# Drury-DABSC.net
KiCad netlist of a schematic drawn in EAGLE
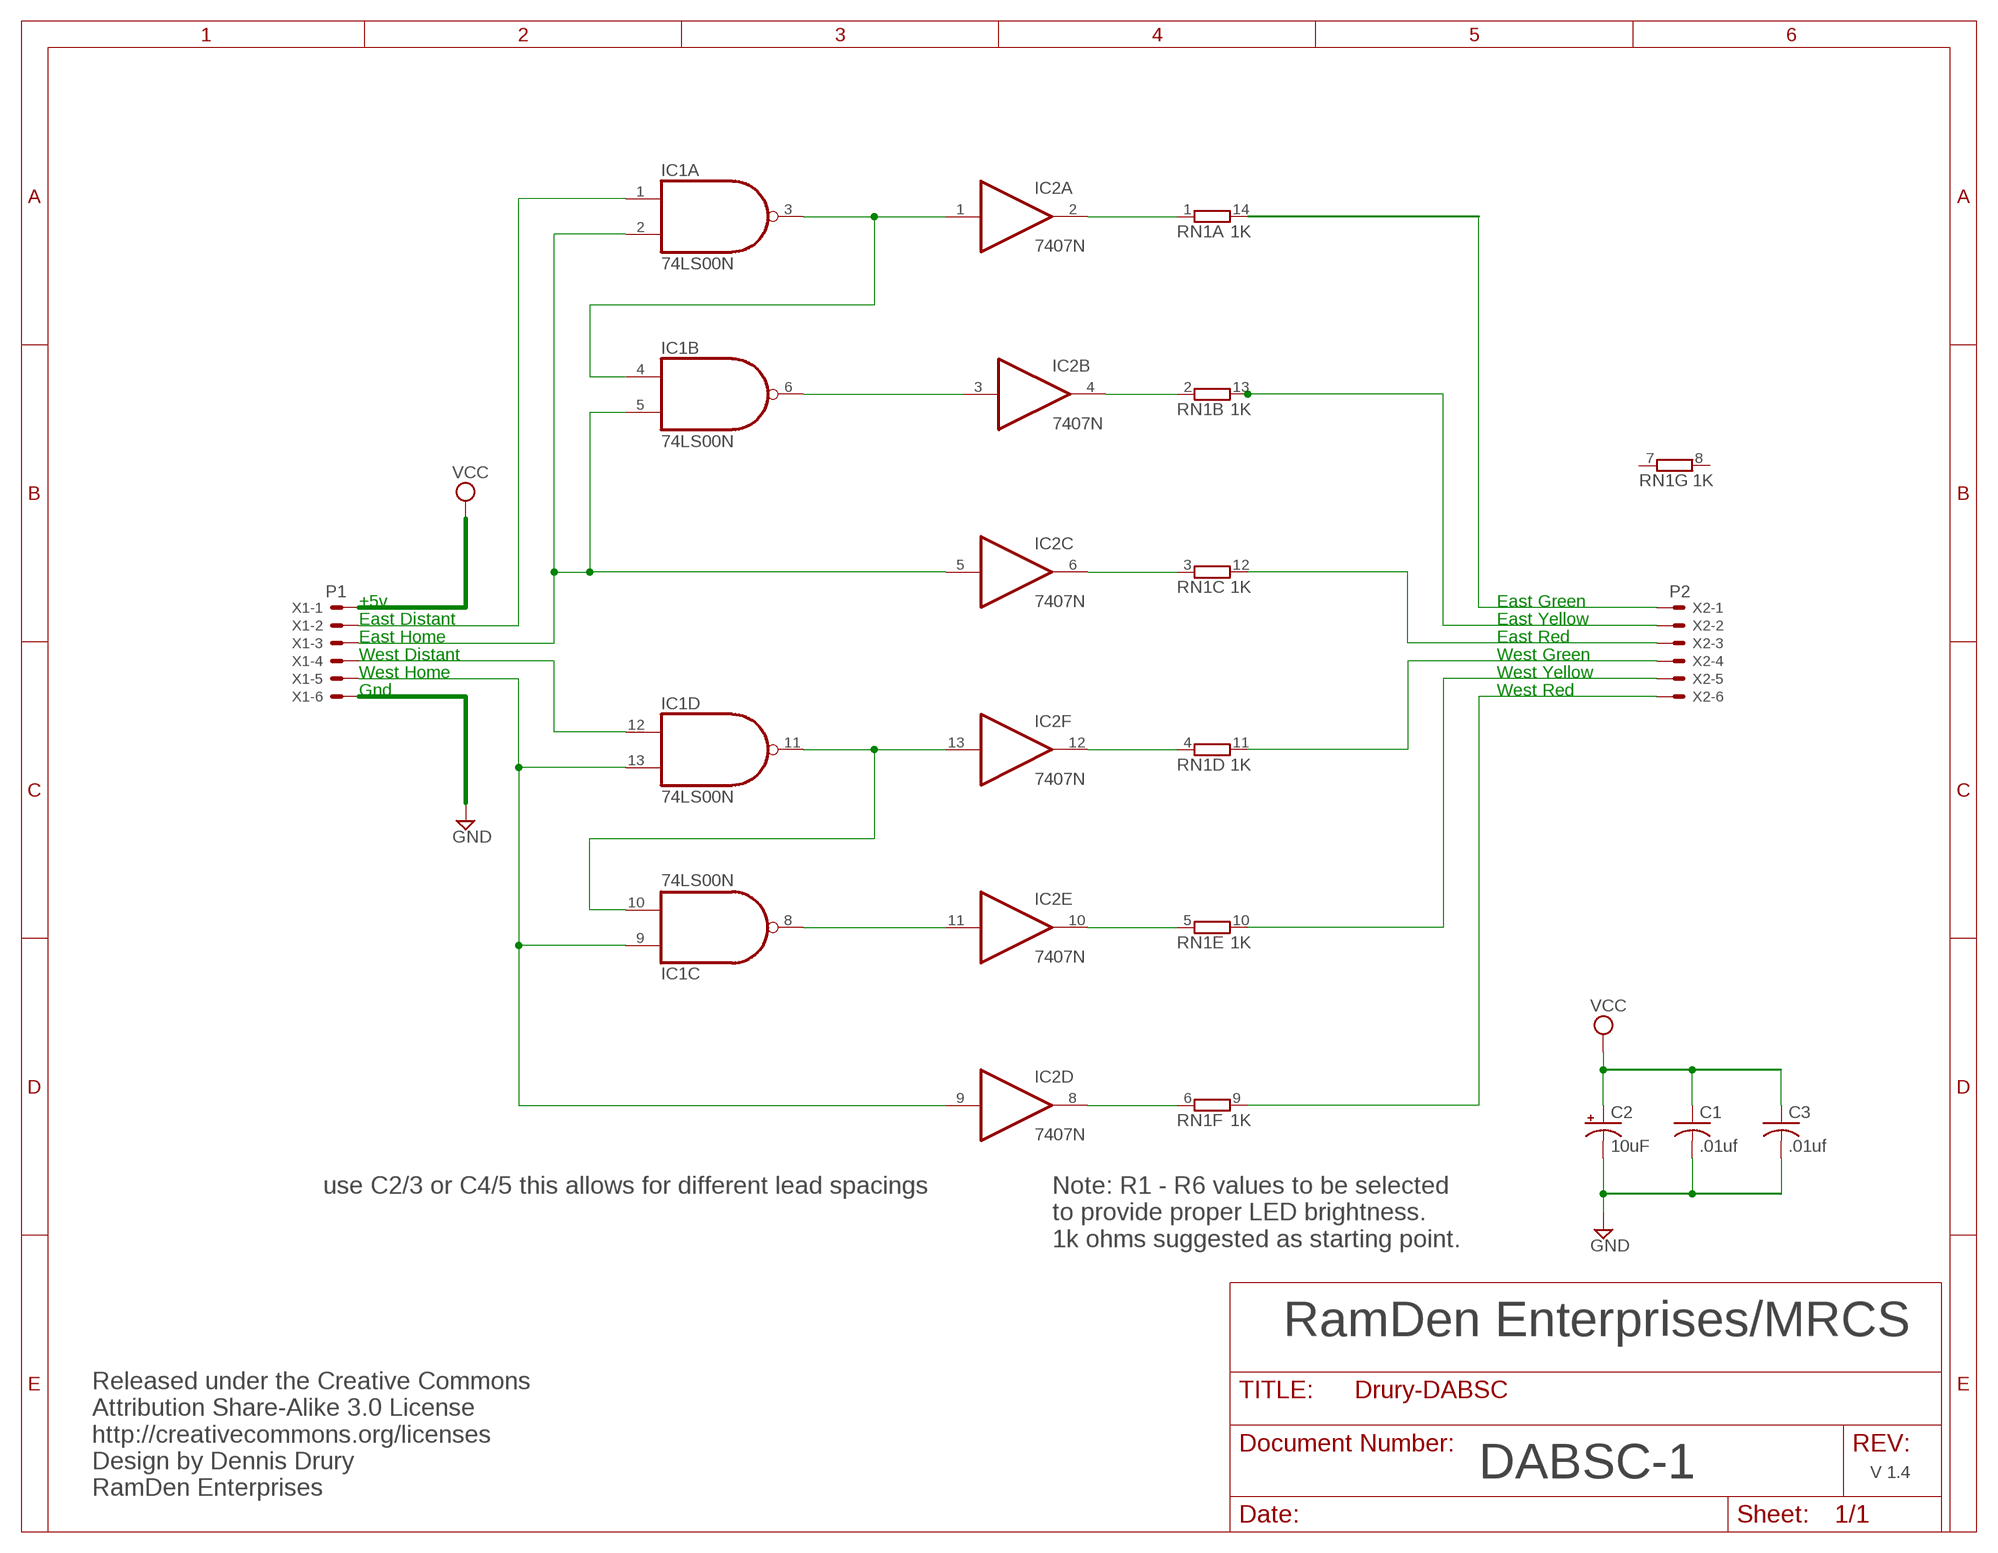
[diagram p0: schematic, sheet 1]

(export (version "E")
  (design (tool "Eeschema 10.0.6"))
  (components
    (comp (ref "C1")
      (value ".01uf")
      (footprint "eagle-import:C050-025X075")
      (libsource (lib "eagle-import") (part "C-US050-025X075"))
    )
    (comp (ref "C2")
      (value "10uF")
      (footprint "eagle-import:E2-5")
      (libsource (lib "eagle-import") (part "CAP-POLPTH-2MM"))
    )
    (comp (ref "C3")
      (value ".01uf")
      (footprint "eagle-import:C050-025X075")
      (libsource (lib "eagle-import") (part "C-US050-025X075"))
    )
    (comp (ref "IC1")
      (value "74LS00N")
      (footprint "eagle-import:DIL14")
      (libsource (lib "eagle-import") (part "7400NLS"))
    )
    (comp (ref "IC2")
      (value "7407N")
      (footprint "eagle-import:DIL14")
      (libsource (lib "eagle-import") (part "7407N"))
    )
    (comp (ref "RN1")
      (value "1K")
      (footprint "eagle-import:DIL14")
      (libsource (lib "eagle-import") (part "7R-N"))
    )
    (comp (ref "X1")
      (value "P1")
      (footprint "eagle-import:22-23-2061")
      (fields (field (name "MF") "MOLEX") (field (name "MPN") "22-23-2061"))
      (libsource (lib "eagle-import") (part "22-23-2061"))
    )
    (comp (ref "X2")
      (value "P2")
      (footprint "eagle-import:22-23-2061")
      (fields (field (name "MF") "MOLEX") (field (name "MPN") "22-23-2061"))
      (libsource (lib "eagle-import") (part "22-23-2061"))
    )
  )
  (nets
    (net (code "1") (name "GND") (class "Default")
      (node (ref "C1") (pin "2") (pinfunction "2_2") (pintype "passive"))
      (node (ref "C2") (pin "-") (pinfunction "-_-") (pintype "passive"))
      (node (ref "C3") (pin "2") (pinfunction "2_2") (pintype "passive"))
      (node (ref "X1") (pin "6") (pinfunction "S_6") (pintype "passive"))
    )
    (net (code "2") (name "Net-(IC1A-I0)") (class "Default")
      (node (ref "IC1") (pin "1") (pinfunction "I0_1") (pintype "input"))
      (node (ref "X1") (pin "2") (pinfunction "S_2") (pintype "passive"))
    )
    (net (code "3") (name "Net-(IC1A-I1)") (class "Default")
      (node (ref "IC1") (pin "2") (pinfunction "I1_2") (pintype "input"))
      (node (ref "IC1") (pin "5") (pinfunction "I1_5") (pintype "input"))
      (node (ref "IC2") (pin "5") (pinfunction "I_5") (pintype "input"))
      (node (ref "X1") (pin "3") (pinfunction "S_3") (pintype "passive"))
    )
    (net (code "4") (name "Net-(IC1A-O)") (class "Default")
      (node (ref "IC1") (pin "3") (pinfunction "O_3") (pintype "output"))
      (node (ref "IC1") (pin "4") (pinfunction "I0_4") (pintype "input"))
      (node (ref "IC2") (pin "1") (pinfunction "I_1") (pintype "input"))
    )
    (net (code "5") (name "Net-(IC1B-O)") (class "Default")
      (node (ref "IC1") (pin "6") (pinfunction "O_6") (pintype "output"))
      (node (ref "IC2") (pin "3") (pinfunction "I_3") (pintype "input"))
    )
    (net (code "6") (name "Net-(IC1C-I0)") (class "Default")
      (node (ref "IC1") (pin "13") (pinfunction "I1_13") (pintype "input"))
      (node (ref "IC1") (pin "9") (pinfunction "I0_9") (pintype "input"))
      (node (ref "IC2") (pin "9") (pinfunction "I_9") (pintype "input"))
      (node (ref "X1") (pin "5") (pinfunction "S_5") (pintype "passive"))
    )
    (net (code "7") (name "Net-(IC1C-I1)") (class "Default")
      (node (ref "IC1") (pin "10") (pinfunction "I1_10") (pintype "input"))
      (node (ref "IC1") (pin "11") (pinfunction "O_11") (pintype "output"))
      (node (ref "IC2") (pin "13") (pinfunction "I_13") (pintype "input"))
    )
    (net (code "8") (name "Net-(IC1C-O)") (class "Default")
      (node (ref "IC1") (pin "8") (pinfunction "O_8") (pintype "output"))
      (node (ref "IC2") (pin "11") (pinfunction "I_11") (pintype "input"))
    )
    (net (code "9") (name "Net-(IC1D-I0)") (class "Default")
      (node (ref "IC1") (pin "12") (pinfunction "I0_12") (pintype "input"))
      (node (ref "X1") (pin "4") (pinfunction "S_4") (pintype "passive"))
    )
    (net (code "10") (name "Net-(IC2A-O)") (class "Default")
      (node (ref "IC2") (pin "2") (pinfunction "O_2") (pintype "open_collector"))
      (node (ref "RN1") (pin "1") (pinfunction "1_1") (pintype "passive"))
    )
    (net (code "11") (name "Net-(IC2B-O)") (class "Default")
      (node (ref "IC2") (pin "4") (pinfunction "O_4") (pintype "open_collector"))
      (node (ref "RN1") (pin "2") (pinfunction "1_2") (pintype "passive"))
    )
    (net (code "12") (name "Net-(IC2C-O)") (class "Default")
      (node (ref "IC2") (pin "6") (pinfunction "O_6") (pintype "open_collector"))
      (node (ref "RN1") (pin "3") (pinfunction "1_3") (pintype "passive"))
    )
    (net (code "13") (name "Net-(IC2D-O)") (class "Default")
      (node (ref "IC2") (pin "8") (pinfunction "O_8") (pintype "open_collector"))
      (node (ref "RN1") (pin "6") (pinfunction "1_6") (pintype "passive"))
    )
    (net (code "14") (name "Net-(IC2E-O)") (class "Default")
      (node (ref "IC2") (pin "10") (pinfunction "O_10") (pintype "open_collector"))
      (node (ref "RN1") (pin "5") (pinfunction "1_5") (pintype "passive"))
    )
    (net (code "15") (name "Net-(IC2F-O)") (class "Default")
      (node (ref "IC2") (pin "12") (pinfunction "O_12") (pintype "open_collector"))
      (node (ref "RN1") (pin "4") (pinfunction "1_4") (pintype "passive"))
    )
    (net (code "16") (name "Net-(RN1A-2)") (class "Default")
      (node (ref "RN1") (pin "14") (pinfunction "2_14") (pintype "passive"))
      (node (ref "X2") (pin "1") (pinfunction "S_1") (pintype "passive"))
    )
    (net (code "17") (name "Net-(RN1B-2)") (class "Default")
      (node (ref "RN1") (pin "13") (pinfunction "2_13") (pintype "passive"))
      (node (ref "X2") (pin "2") (pinfunction "S_2") (pintype "passive"))
    )
    (net (code "18") (name "Net-(RN1C-2)") (class "Default")
      (node (ref "RN1") (pin "12") (pinfunction "2_12") (pintype "passive"))
      (node (ref "X2") (pin "3") (pinfunction "S_3") (pintype "passive"))
    )
    (net (code "19") (name "Net-(RN1D-2)") (class "Default")
      (node (ref "RN1") (pin "11") (pinfunction "2_11") (pintype "passive"))
      (node (ref "X2") (pin "4") (pinfunction "S_4") (pintype "passive"))
    )
    (net (code "20") (name "Net-(RN1E-2)") (class "Default")
      (node (ref "RN1") (pin "10") (pinfunction "2_10") (pintype "passive"))
      (node (ref "X2") (pin "5") (pinfunction "S_5") (pintype "passive"))
    )
    (net (code "21") (name "Net-(RN1F-2)") (class "Default")
      (node (ref "RN1") (pin "9") (pinfunction "2_9") (pintype "passive"))
      (node (ref "X2") (pin "6") (pinfunction "S_6") (pintype "passive"))
    )
    (net (code "22") (name "VCC") (class "Default")
      (node (ref "C1") (pin "1") (pinfunction "1_1") (pintype "passive"))
      (node (ref "C2") (pin "+") (pinfunction "+_+") (pintype "passive"))
      (node (ref "C3") (pin "1") (pinfunction "1_1") (pintype "passive"))
      (node (ref "X1") (pin "1") (pinfunction "S_1") (pintype "passive"))
    )
    (net (code "23") (name "unconnected-(RN1G-1-Pad7)") (class "Default")
      (node (ref "RN1") (pin "7") (pinfunction "1_7") (pintype "passive"))
    )
    (net (code "24") (name "unconnected-(RN1G-2-Pad8)") (class "Default")
      (node (ref "RN1") (pin "8") (pinfunction "2_8") (pintype "passive"))
    )
  )
)
